# xr_vco_components_manual_rt1-V2.net
KiCad netlist of a schematic drawn in EAGLE
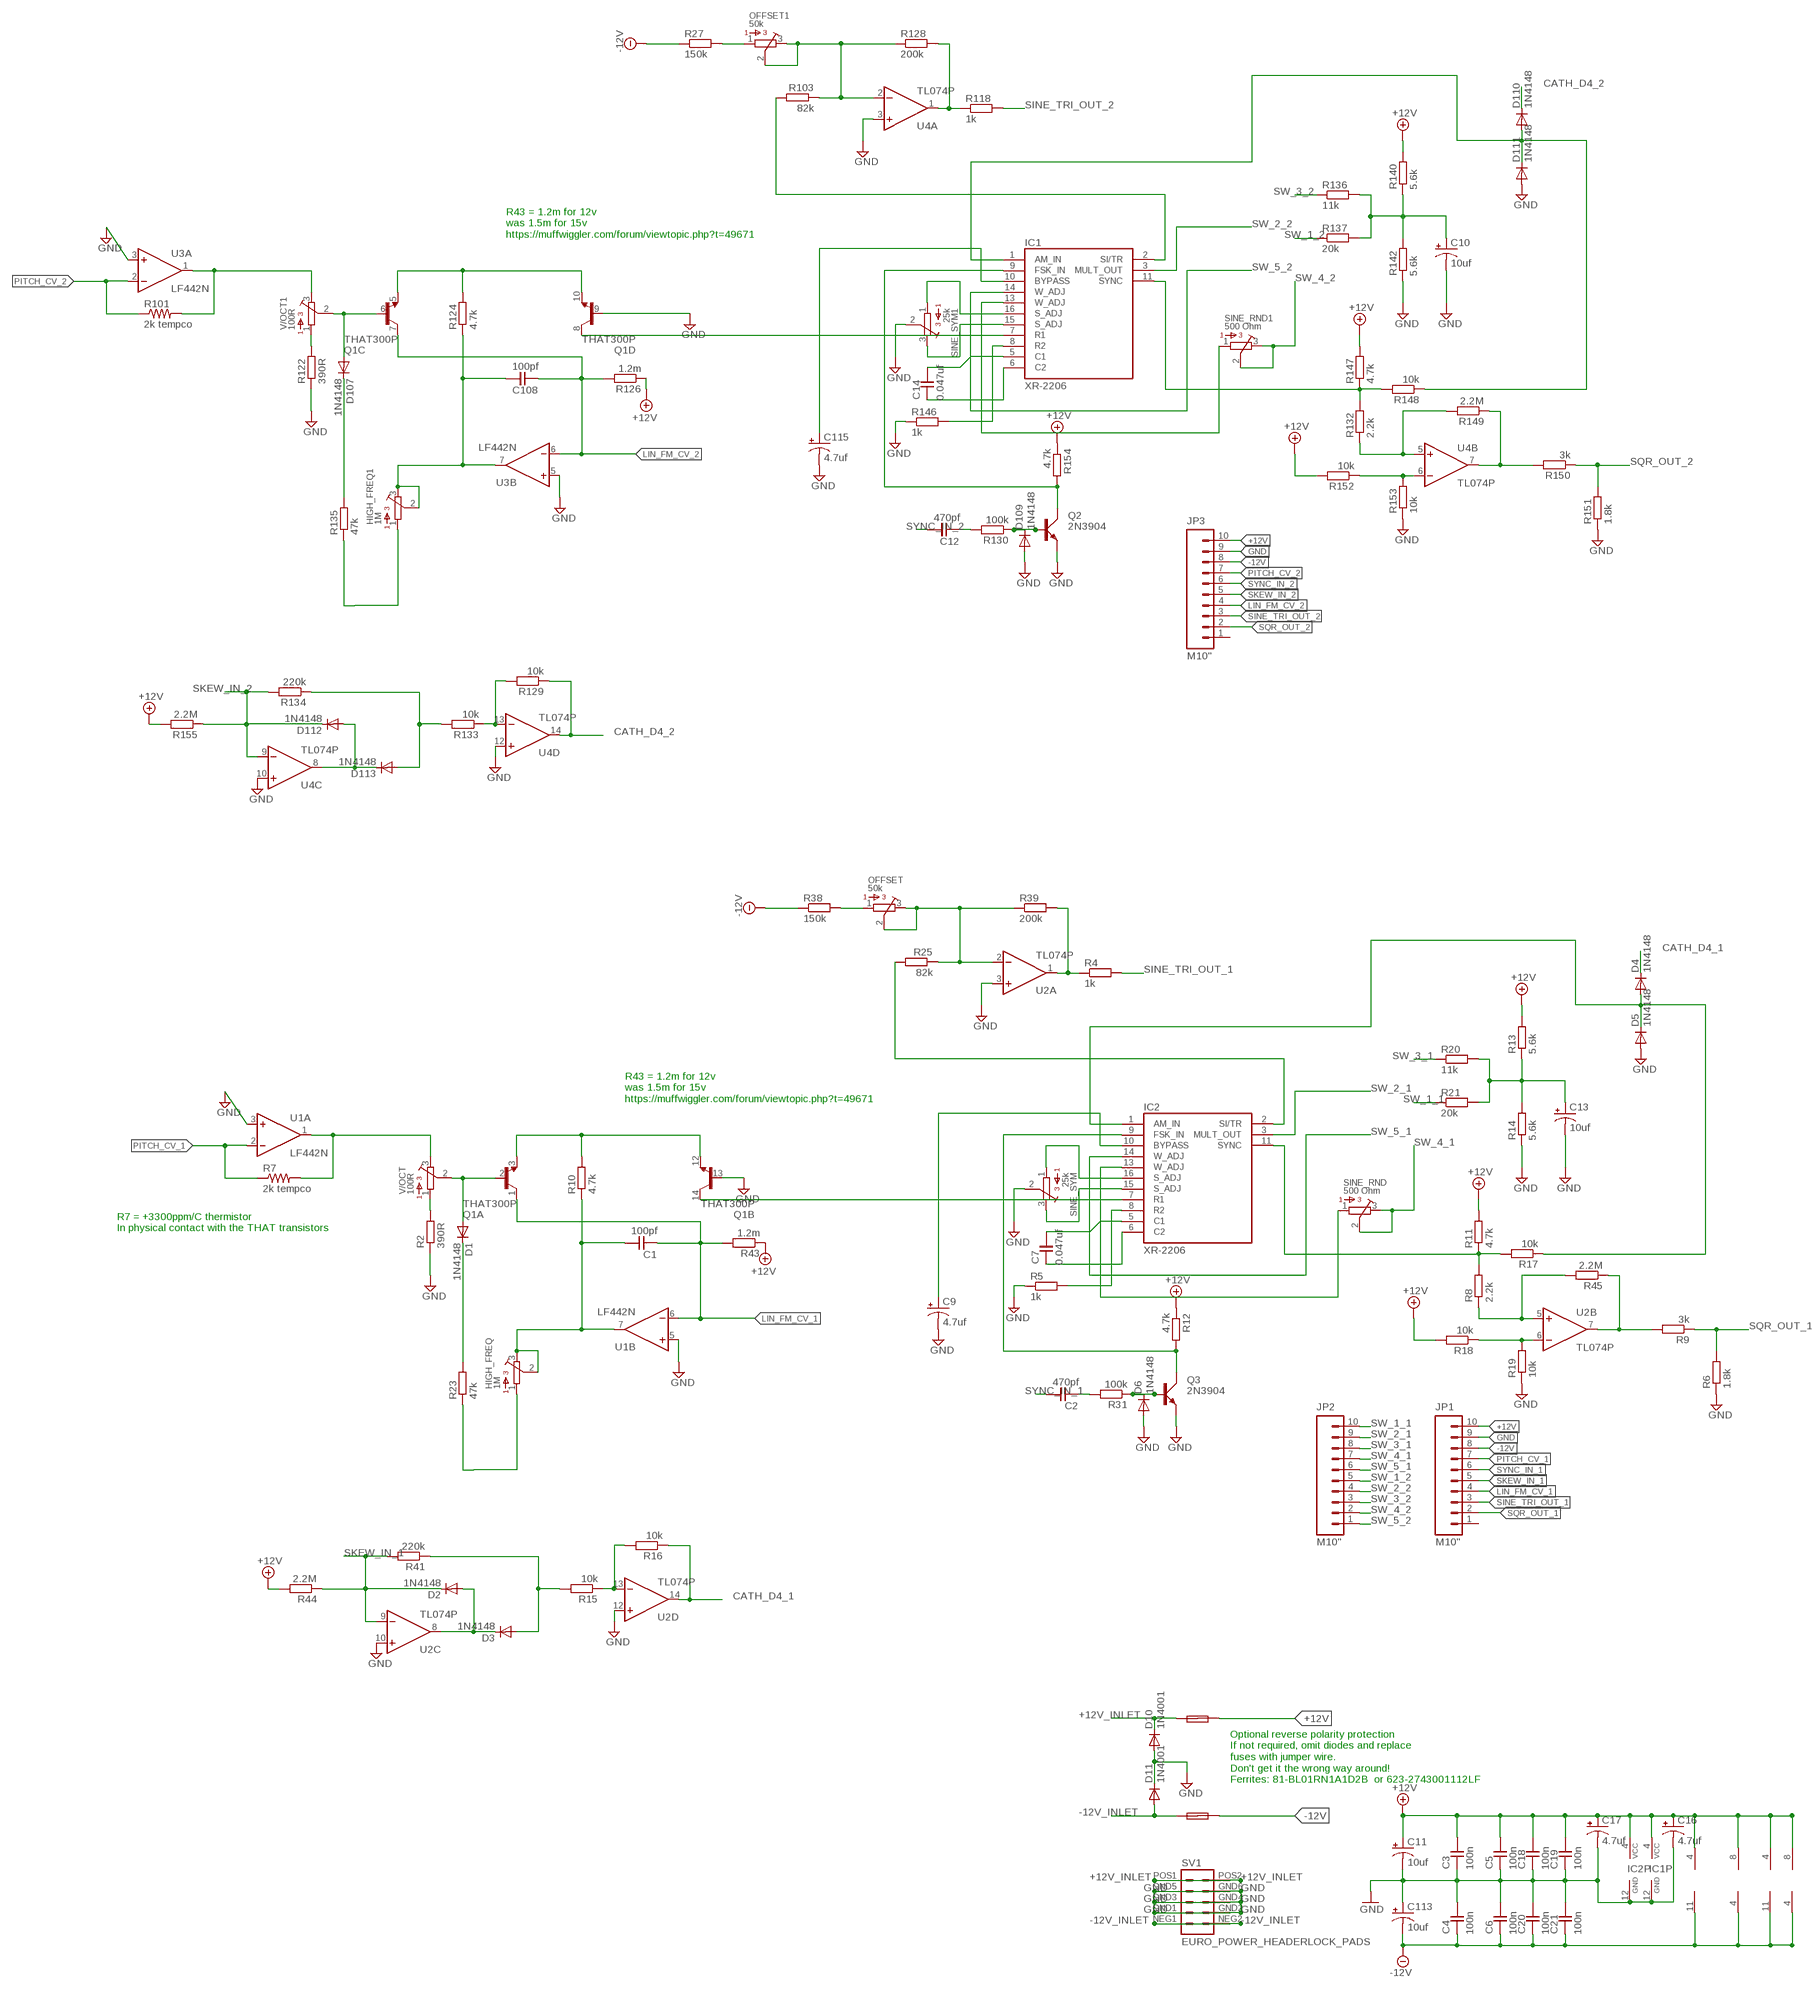
[diagram p0: schematic, sheet 1]

(export (version "E")
  (design (tool "Eeschema 10.0.6"))
  (components
    (comp (ref "C1")
      (value "100pf")
      (footprint "eagle-import:C050-024X044")
      (libsource (lib "eagle-import") (part "C-EU050-024X044"))
    )
    (comp (ref "C2")
      (value "470pf")
      (footprint "eagle-import:C050-024X044")
      (libsource (lib "eagle-import") (part "C-EU050-024X044"))
    )
    (comp (ref "C3")
      (value "100n")
      (footprint "eagle-import:C050-024X044")
      (libsource (lib "eagle-import") (part "C-EU050-024X044"))
    )
    (comp (ref "C4")
      (value "100n")
      (footprint "eagle-import:C050-024X044")
      (libsource (lib "eagle-import") (part "C-EU050-024X044"))
    )
    (comp (ref "C5")
      (value "100n")
      (footprint "eagle-import:C050-024X044")
      (libsource (lib "eagle-import") (part "C-EU050-024X044"))
    )
    (comp (ref "C6")
      (value "100n")
      (footprint "eagle-import:C050-024X044")
      (libsource (lib "eagle-import") (part "C-EU050-024X044"))
    )
    (comp (ref "C7")
      (value "0.047uf")
      (footprint "eagle-import:C050-024X044")
      (libsource (lib "eagle-import") (part "C-EU050-024X044"))
    )
    (comp (ref "C9")
      (value "4.7uf")
      (footprint "eagle-import:CPOL-RADIAL-10UF-25V")
      (libsource (lib "eagle-import") (part "CAP_POLPTH2"))
    )
    (comp (ref "C10")
      (value "10uf")
      (footprint "eagle-import:CPOL-RADIAL-10UF-25V")
      (libsource (lib "eagle-import") (part "CAP_POLPTH2"))
    )
    (comp (ref "C11")
      (value "10uf")
      (footprint "eagle-import:CPOL-RADIAL-10UF-25V")
      (libsource (lib "eagle-import") (part "CAP_POLPTH2"))
    )
    (comp (ref "C12")
      (value "470pf")
      (footprint "eagle-import:C050-024X044")
      (libsource (lib "eagle-import") (part "C-EU050-024X044"))
    )
    (comp (ref "C13")
      (value "10uf")
      (footprint "eagle-import:CPOL-RADIAL-10UF-25V")
      (libsource (lib "eagle-import") (part "CAP_POLPTH2"))
    )
    (comp (ref "C14")
      (value "0.047uf")
      (footprint "eagle-import:C050-024X044")
      (libsource (lib "eagle-import") (part "C-EU050-024X044"))
    )
    (comp (ref "C16")
      (value "4.7uf")
      (footprint "eagle-import:CPOL-RADIAL-10UF-25V")
      (libsource (lib "eagle-import") (part "CAP_POLPTH2"))
    )
    (comp (ref "C17")
      (value "4.7uf")
      (footprint "eagle-import:CPOL-RADIAL-10UF-25V")
      (libsource (lib "eagle-import") (part "CAP_POLPTH2"))
    )
    (comp (ref "C18")
      (value "100n")
      (footprint "eagle-import:C050-024X044")
      (libsource (lib "eagle-import") (part "C-EU050-024X044"))
    )
    (comp (ref "C19")
      (value "100n")
      (footprint "eagle-import:C050-024X044")
      (libsource (lib "eagle-import") (part "C-EU050-024X044"))
    )
    (comp (ref "C20")
      (value "100n")
      (footprint "eagle-import:C050-024X044")
      (libsource (lib "eagle-import") (part "C-EU050-024X044"))
    )
    (comp (ref "C21")
      (value "100n")
      (footprint "eagle-import:C050-024X044")
      (libsource (lib "eagle-import") (part "C-EU050-024X044"))
    )
    (comp (ref "C108")
      (value "100pf")
      (footprint "eagle-import:C050-024X044")
      (libsource (lib "eagle-import") (part "C-EU050-024X044"))
    )
    (comp (ref "C113")
      (value "10uf")
      (footprint "eagle-import:CPOL-RADIAL-10UF-25V")
      (libsource (lib "eagle-import") (part "CAP_POLPTH2"))
    )
    (comp (ref "C115")
      (value "4.7uf")
      (footprint "eagle-import:CPOL-RADIAL-10UF-25V")
      (libsource (lib "eagle-import") (part "CAP_POLPTH2"))
    )
    (comp (ref "D1")
      (value "1N4148")
      (footprint "eagle-import:DO35-7")
      (libsource (lib "eagle-import") (part "SMALL_DIODEDO35-7"))
    )
    (comp (ref "D2")
      (value "1N4148")
      (footprint "eagle-import:DO35-7")
      (libsource (lib "eagle-import") (part "SMALL_DIODEDO35-7"))
    )
    (comp (ref "D3")
      (value "1N4148")
      (footprint "eagle-import:DO35-7")
      (libsource (lib "eagle-import") (part "SMALL_DIODEDO35-7"))
    )
    (comp (ref "D4")
      (value "1N4148")
      (footprint "eagle-import:DO35-7")
      (libsource (lib "eagle-import") (part "SMALL_DIODEDO35-7"))
    )
    (comp (ref "D5")
      (value "1N4148")
      (footprint "eagle-import:DO35-7")
      (libsource (lib "eagle-import") (part "SMALL_DIODEDO35-7"))
    )
    (comp (ref "D6")
      (value "1N4148")
      (footprint "eagle-import:DO35-7")
      (libsource (lib "eagle-import") (part "SMALL_DIODEDO35-7"))
    )
    (comp (ref "D10")
      (value "1N4001")
      (footprint "eagle-import:DO41-10")
      (libsource (lib "eagle-import") (part "1N4004"))
    )
    (comp (ref "D11")
      (value "1N4001")
      (footprint "eagle-import:DO41-10")
      (libsource (lib "eagle-import") (part "1N4004"))
    )
    (comp (ref "D107")
      (value "1N4148")
      (footprint "eagle-import:DO35-7")
      (libsource (lib "eagle-import") (part "SMALL_DIODEDO35-7"))
    )
    (comp (ref "D109")
      (value "1N4148")
      (footprint "eagle-import:DO35-7")
      (libsource (lib "eagle-import") (part "SMALL_DIODEDO35-7"))
    )
    (comp (ref "D110")
      (value "1N4148")
      (footprint "eagle-import:DO35-7")
      (libsource (lib "eagle-import") (part "SMALL_DIODEDO35-7"))
    )
    (comp (ref "D111")
      (value "1N4148")
      (footprint "eagle-import:DO35-7")
      (libsource (lib "eagle-import") (part "SMALL_DIODEDO35-7"))
    )
    (comp (ref "D112")
      (value "1N4148")
      (footprint "eagle-import:DO35-7")
      (libsource (lib "eagle-import") (part "SMALL_DIODEDO35-7"))
    )
    (comp (ref "D113")
      (value "1N4148")
      (footprint "eagle-import:DO35-7")
      (libsource (lib "eagle-import") (part "SMALL_DIODEDO35-7"))
    )
    (comp (ref "F1")
      (value "FUSE")
      (footprint "eagle-import:C050H075X075")
      (libsource (lib "eagle-import") (part "PTC_FUSEPOLY_FUSE"))
    )
    (comp (ref "F2")
      (value "FUSE")
      (footprint "eagle-import:C050H075X075")
      (libsource (lib "eagle-import") (part "PTC_FUSEPOLY_FUSE"))
    )
    (comp (ref "HIGH_FREQ")
      (value "1M")
      (footprint "eagle-import:BOURNS_3362P_TRIMMER")
      (libsource (lib "eagle-import") (part "BOURNS_3362P_TRIMMERP"))
    )
    (comp (ref "HIGH_FREQ1")
      (value "1M")
      (footprint "eagle-import:BOURNS_3362P_TRIMMER")
      (libsource (lib "eagle-import") (part "BOURNS_3362P_TRIMMERP"))
    )
    (comp (ref "IC1")
      (value "XR-2206")
      (footprint "eagle-import:DIL16")
      (libsource (lib "eagle-import") (part "XR-2206"))
    )
    (comp (ref "IC2")
      (value "XR-2206")
      (footprint "eagle-import:DIL16")
      (libsource (lib "eagle-import") (part "XR-2206"))
    )
    (comp (ref "JP1")
      (value "M10\"")
      (footprint "eagle-import:1X10")
      (libsource (lib "eagle-import") (part "M10{dblquote}"))
    )
    (comp (ref "JP2")
      (value "M10\"")
      (footprint "eagle-import:1X10")
      (libsource (lib "eagle-import") (part "M10{dblquote}"))
    )
    (comp (ref "JP3")
      (value "M10\"")
      (footprint "eagle-import:1X10")
      (libsource (lib "eagle-import") (part "M10{dblquote}"))
    )
    (comp (ref "OFFSET")
      (value "50k")
      (footprint "eagle-import:BOURNS_3362P_TRIMMER")
      (libsource (lib "eagle-import") (part "BOURNS_3362P_TRIMMERP"))
    )
    (comp (ref "OFFSET1")
      (value "50k")
      (footprint "eagle-import:BOURNS_3362P_TRIMMER")
      (libsource (lib "eagle-import") (part "BOURNS_3362P_TRIMMERP"))
    )
    (comp (ref "Q1")
      (value "THAT300P")
      (footprint "eagle-import:DIL14")
      (libsource (lib "eagle-import") (part "THAT300P"))
    )
    (comp (ref "Q2")
      (value "2N3904")
      (footprint "eagle-import:TO92D")
      (libsource (lib "eagle-import") (part "2N3904"))
    )
    (comp (ref "Q3")
      (value "2N3904")
      (footprint "eagle-import:TO92D")
      (libsource (lib "eagle-import") (part "2N3904"))
    )
    (comp (ref "R2")
      (value "390R")
      (footprint "eagle-import:7MM_RESISTOR")
      (libsource (lib "eagle-import") (part "RESISTOR7MM"))
    )
    (comp (ref "R4")
      (value "1k")
      (footprint "eagle-import:7MM_RESISTOR")
      (libsource (lib "eagle-import") (part "RESISTOR7MM"))
    )
    (comp (ref "R5")
      (value "1k")
      (footprint "eagle-import:7MM_RESISTOR")
      (libsource (lib "eagle-import") (part "RESISTOR7MM"))
    )
    (comp (ref "R6")
      (value "1.8k")
      (footprint "eagle-import:7MM_RESISTOR")
      (libsource (lib "eagle-import") (part "RESISTOR7MM"))
    )
    (comp (ref "R7")
      (value "2k tempco")
      (footprint "eagle-import:0309_12")
      (libsource (lib "eagle-import") (part "R-US_0309/12"))
    )
    (comp (ref "R8")
      (value "2.2k")
      (footprint "eagle-import:7MM_RESISTOR")
      (libsource (lib "eagle-import") (part "RESISTOR7MM"))
    )
    (comp (ref "R9")
      (value "3k")
      (footprint "eagle-import:7MM_RESISTOR")
      (libsource (lib "eagle-import") (part "RESISTOR7MM"))
    )
    (comp (ref "R10")
      (value "4.7k")
      (footprint "eagle-import:7MM_RESISTOR")
      (libsource (lib "eagle-import") (part "RESISTOR7MM"))
    )
    (comp (ref "R11")
      (value "4.7k")
      (footprint "eagle-import:7MM_RESISTOR")
      (libsource (lib "eagle-import") (part "RESISTOR7MM"))
    )
    (comp (ref "R12")
      (value "4.7k")
      (footprint "eagle-import:7MM_RESISTOR")
      (libsource (lib "eagle-import") (part "RESISTOR7MM"))
    )
    (comp (ref "R13")
      (value "5.6k")
      (footprint "eagle-import:7MM_RESISTOR")
      (libsource (lib "eagle-import") (part "RESISTOR7MM"))
    )
    (comp (ref "R14")
      (value "5.6k")
      (footprint "eagle-import:7MM_RESISTOR")
      (libsource (lib "eagle-import") (part "RESISTOR7MM"))
    )
    (comp (ref "R15")
      (value "10k")
      (footprint "eagle-import:7MM_RESISTOR")
      (libsource (lib "eagle-import") (part "RESISTOR7MM"))
    )
    (comp (ref "R16")
      (value "10k")
      (footprint "eagle-import:7MM_RESISTOR")
      (libsource (lib "eagle-import") (part "RESISTOR7MM"))
    )
    (comp (ref "R17")
      (value "10k")
      (footprint "eagle-import:7MM_RESISTOR")
      (libsource (lib "eagle-import") (part "RESISTOR7MM"))
    )
    (comp (ref "R18")
      (value "10k")
      (footprint "eagle-import:7MM_RESISTOR")
      (libsource (lib "eagle-import") (part "RESISTOR7MM"))
    )
    (comp (ref "R19")
      (value "10k")
      (footprint "eagle-import:7MM_RESISTOR")
      (libsource (lib "eagle-import") (part "RESISTOR7MM"))
    )
    (comp (ref "R20")
      (value "11k")
      (footprint "eagle-import:7MM_RESISTOR")
      (libsource (lib "eagle-import") (part "RESISTOR7MM"))
    )
    (comp (ref "R21")
      (value "20k")
      (footprint "eagle-import:7MM_RESISTOR")
      (libsource (lib "eagle-import") (part "RESISTOR7MM"))
    )
    (comp (ref "R23")
      (value "47k")
      (footprint "eagle-import:7MM_RESISTOR")
      (libsource (lib "eagle-import") (part "RESISTOR7MM"))
    )
    (comp (ref "R25")
      (value "82k")
      (footprint "eagle-import:7MM_RESISTOR")
      (libsource (lib "eagle-import") (part "RESISTOR7MM"))
    )
    (comp (ref "R27")
      (value "150k")
      (footprint "eagle-import:7MM_RESISTOR")
      (libsource (lib "eagle-import") (part "RESISTOR7MM"))
    )
    (comp (ref "R31")
      (value "100k")
      (footprint "eagle-import:7MM_RESISTOR")
      (libsource (lib "eagle-import") (part "RESISTOR7MM"))
    )
    (comp (ref "R38")
      (value "150k")
      (footprint "eagle-import:7MM_RESISTOR")
      (libsource (lib "eagle-import") (part "RESISTOR7MM"))
    )
    (comp (ref "R39")
      (value "200k")
      (footprint "eagle-import:7MM_RESISTOR")
      (libsource (lib "eagle-import") (part "RESISTOR7MM"))
    )
    (comp (ref "R41")
      (value "220k")
      (footprint "eagle-import:7MM_RESISTOR")
      (libsource (lib "eagle-import") (part "RESISTOR7MM"))
    )
    (comp (ref "R43")
      (value "1.2m")
      (footprint "eagle-import:7MM_RESISTOR")
      (libsource (lib "eagle-import") (part "RESISTOR7MM"))
    )
    (comp (ref "R44")
      (value "2.2M")
      (footprint "eagle-import:7MM_RESISTOR")
      (libsource (lib "eagle-import") (part "RESISTOR7MM"))
    )
    (comp (ref "R45")
      (value "2.2M")
      (footprint "eagle-import:7MM_RESISTOR")
      (libsource (lib "eagle-import") (part "RESISTOR7MM"))
    )
    (comp (ref "R101")
      (value "2k tempco")
      (footprint "eagle-import:0309_12")
      (libsource (lib "eagle-import") (part "R-US_0309/12"))
    )
    (comp (ref "R103")
      (value "82k")
      (footprint "eagle-import:7MM_RESISTOR")
      (libsource (lib "eagle-import") (part "RESISTOR7MM"))
    )
    (comp (ref "R118")
      (value "1k")
      (footprint "eagle-import:7MM_RESISTOR")
      (libsource (lib "eagle-import") (part "RESISTOR7MM"))
    )
    (comp (ref "R122")
      (value "390R")
      (footprint "eagle-import:7MM_RESISTOR")
      (libsource (lib "eagle-import") (part "RESISTOR7MM"))
    )
    (comp (ref "R124")
      (value "4.7k")
      (footprint "eagle-import:7MM_RESISTOR")
      (libsource (lib "eagle-import") (part "RESISTOR7MM"))
    )
    (comp (ref "R126")
      (value "1.2m")
      (footprint "eagle-import:7MM_RESISTOR")
      (libsource (lib "eagle-import") (part "RESISTOR7MM"))
    )
    (comp (ref "R128")
      (value "200k")
      (footprint "eagle-import:7MM_RESISTOR")
      (libsource (lib "eagle-import") (part "RESISTOR7MM"))
    )
    (comp (ref "R129")
      (value "10k")
      (footprint "eagle-import:7MM_RESISTOR")
      (libsource (lib "eagle-import") (part "RESISTOR7MM"))
    )
    (comp (ref "R130")
      (value "100k")
      (footprint "eagle-import:7MM_RESISTOR")
      (libsource (lib "eagle-import") (part "RESISTOR7MM"))
    )
    (comp (ref "R132")
      (value "2.2k")
      (footprint "eagle-import:7MM_RESISTOR")
      (libsource (lib "eagle-import") (part "RESISTOR7MM"))
    )
    (comp (ref "R133")
      (value "10k")
      (footprint "eagle-import:7MM_RESISTOR")
      (libsource (lib "eagle-import") (part "RESISTOR7MM"))
    )
    (comp (ref "R134")
      (value "220k")
      (footprint "eagle-import:7MM_RESISTOR")
      (libsource (lib "eagle-import") (part "RESISTOR7MM"))
    )
    (comp (ref "R135")
      (value "47k")
      (footprint "eagle-import:7MM_RESISTOR")
      (libsource (lib "eagle-import") (part "RESISTOR7MM"))
    )
    (comp (ref "R136")
      (value "11k")
      (footprint "eagle-import:7MM_RESISTOR")
      (libsource (lib "eagle-import") (part "RESISTOR7MM"))
    )
    (comp (ref "R137")
      (value "20k")
      (footprint "eagle-import:7MM_RESISTOR")
      (libsource (lib "eagle-import") (part "RESISTOR7MM"))
    )
    (comp (ref "R140")
      (value "5.6k")
      (footprint "eagle-import:7MM_RESISTOR")
      (libsource (lib "eagle-import") (part "RESISTOR7MM"))
    )
    (comp (ref "R142")
      (value "5.6k")
      (footprint "eagle-import:7MM_RESISTOR")
      (libsource (lib "eagle-import") (part "RESISTOR7MM"))
    )
    (comp (ref "R146")
      (value "1k")
      (footprint "eagle-import:7MM_RESISTOR")
      (libsource (lib "eagle-import") (part "RESISTOR7MM"))
    )
    (comp (ref "R147")
      (value "4.7k")
      (footprint "eagle-import:7MM_RESISTOR")
      (libsource (lib "eagle-import") (part "RESISTOR7MM"))
    )
    (comp (ref "R148")
      (value "10k")
      (footprint "eagle-import:7MM_RESISTOR")
      (libsource (lib "eagle-import") (part "RESISTOR7MM"))
    )
    (comp (ref "R149")
      (value "2.2M")
      (footprint "eagle-import:7MM_RESISTOR")
      (libsource (lib "eagle-import") (part "RESISTOR7MM"))
    )
    (comp (ref "R150")
      (value "3k")
      (footprint "eagle-import:7MM_RESISTOR")
      (libsource (lib "eagle-import") (part "RESISTOR7MM"))
    )
    (comp (ref "R151")
      (value "1.8k")
      (footprint "eagle-import:7MM_RESISTOR")
      (libsource (lib "eagle-import") (part "RESISTOR7MM"))
    )
    (comp (ref "R152")
      (value "10k")
      (footprint "eagle-import:7MM_RESISTOR")
      (libsource (lib "eagle-import") (part "RESISTOR7MM"))
    )
    (comp (ref "R153")
      (value "10k")
      (footprint "eagle-import:7MM_RESISTOR")
      (libsource (lib "eagle-import") (part "RESISTOR7MM"))
    )
    (comp (ref "R154")
      (value "4.7k")
      (footprint "eagle-import:7MM_RESISTOR")
      (libsource (lib "eagle-import") (part "RESISTOR7MM"))
    )
    (comp (ref "R155")
      (value "2.2M")
      (footprint "eagle-import:7MM_RESISTOR")
      (libsource (lib "eagle-import") (part "RESISTOR7MM"))
    )
    (comp (ref "SINE_RND")
      (value "500 Ohm")
      (footprint "eagle-import:BOURNS_3362P_TRIMMER")
      (libsource (lib "eagle-import") (part "BOURNS_3362P_TRIMMERP"))
    )
    (comp (ref "SINE_RND1")
      (value "500 Ohm")
      (footprint "eagle-import:BOURNS_3362P_TRIMMER")
      (libsource (lib "eagle-import") (part "BOURNS_3362P_TRIMMERP"))
    )
    (comp (ref "SINE_SYM")
      (value "25k")
      (footprint "eagle-import:BOURNS_3362P_TRIMMER")
      (libsource (lib "eagle-import") (part "BOURNS_3362P_TRIMMERP"))
    )
    (comp (ref "SINE_SYM1")
      (value "25k")
      (footprint "eagle-import:BOURNS_3362P_TRIMMER")
      (libsource (lib "eagle-import") (part "BOURNS_3362P_TRIMMERP"))
    )
    (comp (ref "SV1")
      (value "EURO_POWER_HEADERLOCK_PADS")
      (footprint "eagle-import:EURO_PWR_HEADER_LOCK")
      (libsource (lib "eagle-import") (part "EURO_POWER_HEADERLOCK_PADS"))
    )
    (comp (ref "U1")
      (value "LF442N")
      (footprint "eagle-import:DIL08")
      (libsource (lib "eagle-import") (part "LF442N"))
    )
    (comp (ref "U2")
      (value "TL074P")
      (footprint "eagle-import:DIL14")
      (libsource (lib "eagle-import") (part "TL074P"))
    )
    (comp (ref "U3")
      (value "LF442N")
      (footprint "eagle-import:DIL08")
      (libsource (lib "eagle-import") (part "LF442N"))
    )
    (comp (ref "U4")
      (value "TL074P")
      (footprint "eagle-import:DIL14")
      (libsource (lib "eagle-import") (part "TL074P"))
    )
    (comp (ref "V/OCT")
      (value "100R")
      (footprint "eagle-import:BOURNS_3362P_TRIMMER")
      (libsource (lib "eagle-import") (part "BOURNS_3362P_TRIMMERP"))
    )
    (comp (ref "V/OCT1")
      (value "100R")
      (footprint "eagle-import:BOURNS_3362P_TRIMMER")
      (libsource (lib "eagle-import") (part "BOURNS_3362P_TRIMMERP"))
    )
  )
  (nets
    (net (code "1") (name "+12V") (class "Default")
      (node (ref "C11") (pin "1") (pinfunction "+_1") (pintype "passive"))
      (node (ref "C16") (pin "1") (pinfunction "+_1") (pintype "passive"))
      (node (ref "C17") (pin "1") (pinfunction "+_1") (pintype "passive"))
      (node (ref "C18") (pin "1") (pinfunction "1_1") (pintype "passive"))
      (node (ref "C19") (pin "1") (pinfunction "1_1") (pintype "passive"))
      (node (ref "C3") (pin "1") (pinfunction "1_1") (pintype "passive"))
      (node (ref "C5") (pin "1") (pinfunction "1_1") (pintype "passive"))
      (node (ref "F1") (pin "2") (pinfunction "P$2_2") (pintype "bidirectional"))
      (node (ref "IC1") (pin "4") (pinfunction "VCC_4") (pintype "power_in"))
      (node (ref "IC2") (pin "4") (pinfunction "VCC_4") (pintype "power_in"))
      (node (ref "JP1") (pin "10") (pinfunction "10_10") (pintype "passive"))
      (node (ref "JP3") (pin "10") (pinfunction "10_10") (pintype "passive"))
      (node (ref "R11") (pin "2") (pinfunction "2_2") (pintype "passive"))
      (node (ref "R12") (pin "1") (pinfunction "1_1") (pintype "passive"))
      (node (ref "R126") (pin "1") (pinfunction "1_1") (pintype "passive"))
      (node (ref "R13") (pin "2") (pinfunction "2_2") (pintype "passive"))
      (node (ref "R140") (pin "2") (pinfunction "2_2") (pintype "passive"))
      (node (ref "R147") (pin "2") (pinfunction "2_2") (pintype "passive"))
      (node (ref "R152") (pin "2") (pinfunction "2_2") (pintype "passive"))
      (node (ref "R154") (pin "1") (pinfunction "1_1") (pintype "passive"))
      (node (ref "R155") (pin "2") (pinfunction "2_2") (pintype "passive"))
      (node (ref "R18") (pin "2") (pinfunction "2_2") (pintype "passive"))
      (node (ref "R43") (pin "1") (pinfunction "1_1") (pintype "passive"))
      (node (ref "R44") (pin "2") (pinfunction "2_2") (pintype "passive"))
      (node (ref "U1") (pin "8") (pinfunction "V+_8") (pintype "power_in"))
      (node (ref "U2") (pin "4") (pinfunction "V+_4") (pintype "power_in"))
      (node (ref "U3") (pin "8") (pinfunction "V+_8") (pintype "power_in"))
      (node (ref "U4") (pin "4") (pinfunction "V+_4") (pintype "power_in"))
    )
    (net (code "2") (name "-12V") (class "Default")
      (node (ref "C113") (pin "2") (pinfunction "-_2") (pintype "passive"))
      (node (ref "C20") (pin "2") (pinfunction "2_2") (pintype "passive"))
      (node (ref "C21") (pin "2") (pinfunction "2_2") (pintype "passive"))
      (node (ref "C4") (pin "2") (pinfunction "2_2") (pintype "passive"))
      (node (ref "C6") (pin "2") (pinfunction "2_2") (pintype "passive"))
      (node (ref "F2") (pin "2") (pinfunction "P$2_2") (pintype "bidirectional"))
      (node (ref "JP1") (pin "8") (pinfunction "8_8") (pintype "passive"))
      (node (ref "JP3") (pin "8") (pinfunction "8_8") (pintype "passive"))
      (node (ref "R27") (pin "1") (pinfunction "1_1") (pintype "passive"))
      (node (ref "R38") (pin "1") (pinfunction "1_1") (pintype "passive"))
      (node (ref "U1") (pin "4") (pinfunction "V-_4") (pintype "power_in"))
      (node (ref "U2") (pin "11") (pinfunction "V-_11") (pintype "power_in"))
      (node (ref "U3") (pin "4") (pinfunction "V-_4") (pintype "power_in"))
      (node (ref "U4") (pin "11") (pinfunction "V-_11") (pintype "power_in"))
    )
    (net (code "3") (name "/+12V_INLET") (class "Default")
      (node (ref "D10") (pin "C") (pinfunction "C_C") (pintype "passive"))
      (node (ref "F1") (pin "1") (pinfunction "P$1_1") (pintype "bidirectional"))
      (node (ref "SV1") (pin "POS1") (pinfunction "10_POS1") (pintype "passive"))
      (node (ref "SV1") (pin "POS2") (pinfunction "9_POS2") (pintype "passive"))
    )
    (net (code "4") (name "/-12V_INLET") (class "Default")
      (node (ref "D11") (pin "A") (pinfunction "A_A") (pintype "passive"))
      (node (ref "F2") (pin "1") (pinfunction "P$1_1") (pintype "bidirectional"))
      (node (ref "SV1") (pin "NEG1") (pinfunction "2_NEG1") (pintype "passive"))
      (node (ref "SV1") (pin "NEG2") (pinfunction "1_NEG2") (pintype "passive"))
    )
    (net (code "5") (name "/CATH_D4_1") (class "Default")
      (node (ref "D4") (pin "C") (pinfunction "C_C") (pintype "passive"))
      (node (ref "R16") (pin "1") (pinfunction "1_1") (pintype "passive"))
      (node (ref "U2") (pin "14") (pinfunction "OUT_14") (pintype "output"))
    )
    (net (code "6") (name "/CATH_D4_2") (class "Default")
      (node (ref "D110") (pin "C") (pinfunction "C_C") (pintype "passive"))
      (node (ref "R129") (pin "1") (pinfunction "1_1") (pintype "passive"))
      (node (ref "U4") (pin "14") (pinfunction "OUT_14") (pintype "output"))
    )
    (net (code "7") (name "/SW_1_1") (class "Default")
      (node (ref "JP2") (pin "10") (pinfunction "10_10") (pintype "passive"))
      (node (ref "R21") (pin "1") (pinfunction "1_1") (pintype "passive"))
    )
    (net (code "8") (name "/SW_1_2") (class "Default")
      (node (ref "JP2") (pin "5") (pinfunction "5_5") (pintype "passive"))
      (node (ref "R137") (pin "1") (pinfunction "1_1") (pintype "passive"))
    )
    (net (code "9") (name "/SW_2_1") (class "Default")
      (node (ref "IC2") (pin "3") (pinfunction "MULT_OUT_3") (pintype "output"))
      (node (ref "JP2") (pin "9") (pinfunction "9_9") (pintype "passive"))
    )
    (net (code "10") (name "/SW_2_2") (class "Default")
      (node (ref "IC1") (pin "3") (pinfunction "MULT_OUT_3") (pintype "output"))
      (node (ref "JP2") (pin "4") (pinfunction "4_4") (pintype "passive"))
    )
    (net (code "11") (name "/SW_3_1") (class "Default")
      (node (ref "JP2") (pin "8") (pinfunction "8_8") (pintype "passive"))
      (node (ref "R20") (pin "1") (pinfunction "1_1") (pintype "passive"))
    )
    (net (code "12") (name "/SW_3_2") (class "Default")
      (node (ref "JP2") (pin "3") (pinfunction "3_3") (pintype "passive"))
      (node (ref "R136") (pin "1") (pinfunction "1_1") (pintype "passive"))
    )
    (net (code "13") (name "/SW_4_1") (class "Default")
      (node (ref "JP2") (pin "7") (pinfunction "7_7") (pintype "passive"))
      (node (ref "SINE_RND") (pin "2") (pinfunction "2_2") (pintype "passive"))
      (node (ref "SINE_RND") (pin "3") (pinfunction "3_3") (pintype "passive"))
    )
    (net (code "14") (name "/SW_4_2") (class "Default")
      (node (ref "JP2") (pin "2") (pinfunction "2_2") (pintype "passive"))
      (node (ref "SINE_RND1") (pin "2") (pinfunction "2_2") (pintype "passive"))
      (node (ref "SINE_RND1") (pin "3") (pinfunction "3_3") (pintype "passive"))
    )
    (net (code "15") (name "/SW_5_1") (class "Default")
      (node (ref "IC2") (pin "14") (pinfunction "W_ADJ_14") (pintype "input"))
      (node (ref "JP2") (pin "6") (pinfunction "6_6") (pintype "passive"))
    )
    (net (code "16") (name "/SW_5_2") (class "Default")
      (node (ref "IC1") (pin "14") (pinfunction "W_ADJ_14") (pintype "input"))
      (node (ref "JP2") (pin "1") (pinfunction "1_1") (pintype "passive"))
    )
    (net (code "17") (name "GND") (class "Default")
      (node (ref "C10") (pin "2") (pinfunction "-_2") (pintype "passive"))
      (node (ref "C11") (pin "2") (pinfunction "-_2") (pintype "passive"))
      (node (ref "C113") (pin "1") (pinfunction "+_1") (pintype "passive"))
      (node (ref "C115") (pin "2") (pinfunction "-_2") (pintype "passive"))
      (node (ref "C13") (pin "2") (pinfunction "-_2") (pintype "passive"))
      (node (ref "C16") (pin "2") (pinfunction "-_2") (pintype "passive"))
      (node (ref "C17") (pin "2") (pinfunction "-_2") (pintype "passive"))
      (node (ref "C18") (pin "2") (pinfunction "2_2") (pintype "passive"))
      (node (ref "C19") (pin "2") (pinfunction "2_2") (pintype "passive"))
      (node (ref "C20") (pin "1") (pinfunction "1_1") (pintype "passive"))
      (node (ref "C21") (pin "1") (pinfunction "1_1") (pintype "passive"))
      (node (ref "C3") (pin "2") (pinfunction "2_2") (pintype "passive"))
      (node (ref "C4") (pin "1") (pinfunction "1_1") (pintype "passive"))
      (node (ref "C5") (pin "2") (pinfunction "2_2") (pintype "passive"))
      (node (ref "C6") (pin "1") (pinfunction "1_1") (pintype "passive"))
      (node (ref "C9") (pin "2") (pinfunction "-_2") (pintype "passive"))
      (node (ref "D10") (pin "A") (pinfunction "A_A") (pintype "passive"))
      (node (ref "D109") (pin "A") (pinfunction "A_A") (pintype "passive"))
      (node (ref "D11") (pin "C") (pinfunction "C_C") (pintype "passive"))
      (node (ref "D111") (pin "A") (pinfunction "A_A") (pintype "passive"))
      (node (ref "D5") (pin "A") (pinfunction "A_A") (pintype "passive"))
      (node (ref "D6") (pin "A") (pinfunction "A_A") (pintype "passive"))
      (node (ref "IC1") (pin "12") (pinfunction "GND_12") (pintype "power_in"))
      (node (ref "IC2") (pin "12") (pinfunction "GND_12") (pintype "power_in"))
      (node (ref "JP1") (pin "9") (pinfunction "9_9") (pintype "passive"))
      (node (ref "JP3") (pin "9") (pinfunction "9_9") (pintype "passive"))
      (node (ref "Q1") (pin "13") (pinfunction "B_13") (pintype "passive"))
      (node (ref "Q1") (pin "9") (pinfunction "B_9") (pintype "passive"))
      (node (ref "Q2") (pin "E") (pinfunction "E_E") (pintype "passive"))
      (node (ref "Q3") (pin "E") (pinfunction "E_E") (pintype "passive"))
      (node (ref "R122") (pin "1") (pinfunction "1_1") (pintype "passive"))
      (node (ref "R14") (pin "1") (pinfunction "1_1") (pintype "passive"))
      (node (ref "R142") (pin "1") (pinfunction "1_1") (pintype "passive"))
      (node (ref "R146") (pin "1") (pinfunction "1_1") (pintype "passive"))
      (node (ref "R151") (pin "1") (pinfunction "1_1") (pintype "passive"))
      (node (ref "R153") (pin "1") (pinfunction "1_1") (pintype "passive"))
      (node (ref "R19") (pin "1") (pinfunction "1_1") (pintype "passive"))
      (node (ref "R2") (pin "1") (pinfunction "1_1") (pintype "passive"))
      (node (ref "R5") (pin "1") (pinfunction "1_1") (pintype "passive"))
      (node (ref "R6") (pin "1") (pinfunction "1_1") (pintype "passive"))
      (node (ref "SINE_SYM") (pin "2") (pinfunction "2_2") (pintype "passive"))
      (node (ref "SINE_SYM1") (pin "2") (pinfunction "2_2") (pintype "passive"))
      (node (ref "SV1") (pin "GND1") (pinfunction "4_GND1") (pintype "passive"))
      (node (ref "SV1") (pin "GND2") (pinfunction "3_GND2") (pintype "passive"))
      (node (ref "SV1") (pin "GND3") (pinfunction "6_GND3") (pintype "passive"))
      (node (ref "SV1") (pin "GND4") (pinfunction "5_GND4") (pintype "passive"))
      (node (ref "SV1") (pin "GND5") (pinfunction "8_GND5") (pintype "passive"))
      (node (ref "SV1") (pin "GND6") (pinfunction "7_GND6") (pintype "passive"))
      (node (ref "U1") (pin "3") (pinfunction "+IN_3") (pintype "input"))
      (node (ref "U1") (pin "5") (pinfunction "+IN_5") (pintype "input"))
      (node (ref "U2") (pin "10") (pinfunction "+IN_10") (pintype "input"))
      (node (ref "U2") (pin "12") (pinfunction "+IN_12") (pintype "input"))
      (node (ref "U2") (pin "3") (pinfunction "+IN_3") (pintype "input"))
      (node (ref "U3") (pin "3") (pinfunction "+IN_3") (pintype "input"))
      (node (ref "U3") (pin "5") (pinfunction "+IN_5") (pintype "input"))
      (node (ref "U4") (pin "10") (pinfunction "+IN_10") (pintype "input"))
      (node (ref "U4") (pin "12") (pinfunction "+IN_12") (pintype "input"))
      (node (ref "U4") (pin "3") (pinfunction "+IN_3") (pintype "input"))
    )
    (net (code "18") (name "LIN_FM_CV_1") (class "Default")
      (node (ref "C1") (pin "2") (pinfunction "2_2") (pintype "passive"))
      (node (ref "JP1") (pin "4") (pinfunction "4_4") (pintype "passive"))
      (node (ref "Q1") (pin "1") (pinfunction "C_1") (pintype "passive"))
      (node (ref "R43") (pin "2") (pinfunction "2_2") (pintype "passive"))
      (node (ref "U1") (pin "6") (pinfunction "-IN_6") (pintype "input"))
    )
    (net (code "19") (name "LIN_FM_CV_2") (class "Default")
      (node (ref "C108") (pin "2") (pinfunction "2_2") (pintype "passive"))
      (node (ref "JP3") (pin "4") (pinfunction "4_4") (pintype "passive"))
      (node (ref "Q1") (pin "7") (pinfunction "C_7") (pintype "passive"))
      (node (ref "R126") (pin "2") (pinfunction "2_2") (pintype "passive"))
      (node (ref "U3") (pin "6") (pinfunction "-IN_6") (pintype "input"))
    )
    (net (code "20") (name "Net-(C2-Pad2)") (class "Default")
      (node (ref "C2") (pin "2") (pinfunction "2_2") (pintype "passive"))
      (node (ref "R31") (pin "2") (pinfunction "2_2") (pintype "passive"))
    )
    (net (code "21") (name "Net-(C9-+)") (class "Default")
      (node (ref "C9") (pin "1") (pinfunction "+_1") (pintype "passive"))
      (node (ref "IC2") (pin "10") (pinfunction "BYPASS_10") (pintype "input"))
    )
    (net (code "22") (name "Net-(C10-+)") (class "Default")
      (node (ref "C10") (pin "1") (pinfunction "+_1") (pintype "passive"))
      (node (ref "R136") (pin "2") (pinfunction "2_2") (pintype "passive"))
      (node (ref "R137") (pin "2") (pinfunction "2_2") (pintype "passive"))
      (node (ref "R140") (pin "1") (pinfunction "1_1") (pintype "passive"))
      (node (ref "R142") (pin "2") (pinfunction "2_2") (pintype "passive"))
    )
    (net (code "23") (name "Net-(C12-Pad2)") (class "Default")
      (node (ref "C12") (pin "2") (pinfunction "2_2") (pintype "passive"))
      (node (ref "R130") (pin "2") (pinfunction "2_2") (pintype "passive"))
    )
    (net (code "24") (name "Net-(C13-+)") (class "Default")
      (node (ref "C13") (pin "1") (pinfunction "+_1") (pintype "passive"))
      (node (ref "R13") (pin "1") (pinfunction "1_1") (pintype "passive"))
      (node (ref "R14") (pin "2") (pinfunction "2_2") (pintype "passive"))
      (node (ref "R20") (pin "2") (pinfunction "2_2") (pintype "passive"))
      (node (ref "R21") (pin "2") (pinfunction "2_2") (pintype "passive"))
    )
    (net (code "25") (name "Net-(C115-+)") (class "Default")
      (node (ref "C115") (pin "1") (pinfunction "+_1") (pintype "passive"))
      (node (ref "IC1") (pin "10") (pinfunction "BYPASS_10") (pintype "input"))
    )
    (net (code "26") (name "Net-(D1-PadC)") (class "Default")
      (node (ref "D1") (pin "C") (pinfunction "C_C") (pintype "passive"))
      (node (ref "R23") (pin "2") (pinfunction "2_2") (pintype "passive"))
    )
    (net (code "27") (name "Net-(D3-PadA)") (class "Default")
      (node (ref "D3") (pin "A") (pinfunction "A_A") (pintype "passive"))
      (node (ref "R15") (pin "2") (pinfunction "2_2") (pintype "passive"))
      (node (ref "R41") (pin "1") (pinfunction "1_1") (pintype "passive"))
    )
    (net (code "28") (name "Net-(D6-PadC)") (class "Default")
      (node (ref "D6") (pin "C") (pinfunction "C_C") (pintype "passive"))
      (node (ref "Q3") (pin "B") (pinfunction "B_B") (pintype "passive"))
      (node (ref "R31") (pin "1") (pinfunction "1_1") (pintype "passive"))
    )
    (net (code "29") (name "Net-(D107-PadC)") (class "Default")
      (node (ref "D107") (pin "C") (pinfunction "C_C") (pintype "passive"))
      (node (ref "R135") (pin "2") (pinfunction "2_2") (pintype "passive"))
    )
    (net (code "30") (name "Net-(D109-PadC)") (class "Default")
      (node (ref "D109") (pin "C") (pinfunction "C_C") (pintype "passive"))
      (node (ref "Q2") (pin "B") (pinfunction "B_B") (pintype "passive"))
      (node (ref "R130") (pin "1") (pinfunction "1_1") (pintype "passive"))
    )
    (net (code "31") (name "Net-(D113-PadA)") (class "Default")
      (node (ref "D113") (pin "A") (pinfunction "A_A") (pintype "passive"))
      (node (ref "R133") (pin "2") (pinfunction "2_2") (pintype "passive"))
      (node (ref "R134") (pin "1") (pinfunction "1_1") (pintype "passive"))
    )
    (net (code "32") (name "Net-(HIGH_FREQ-Pad1)") (class "Default")
      (node (ref "HIGH_FREQ") (pin "1") (pinfunction "1_1") (pintype "passive"))
      (node (ref "R23") (pin "1") (pinfunction "1_1") (pintype "passive"))
    )
    (net (code "33") (name "Net-(HIGH_FREQ1-Pad1)") (class "Default")
      (node (ref "HIGH_FREQ1") (pin "1") (pinfunction "1_1") (pintype "passive"))
      (node (ref "R135") (pin "1") (pinfunction "1_1") (pintype "passive"))
    )
    (net (code "34") (name "Net-(IC1A-AM_IN)") (class "Default")
      (node (ref "D110") (pin "A") (pinfunction "A_A") (pintype "passive"))
      (node (ref "D111") (pin "C") (pinfunction "C_C") (pintype "passive"))
      (node (ref "IC1") (pin "1") (pinfunction "AM_IN_1") (pintype "input"))
      (node (ref "R148") (pin "1") (pinfunction "1_1") (pintype "passive"))
    )
    (net (code "35") (name "Net-(IC1A-C1)") (class "Default")
      (node (ref "C14") (pin "1") (pinfunction "1_1") (pintype "passive"))
      (node (ref "IC1") (pin "5") (pinfunction "C1_5") (pintype "input"))
    )
    (net (code "36") (name "Net-(IC1A-C2)") (class "Default")
      (node (ref "C14") (pin "2") (pinfunction "2_2") (pintype "passive"))
      (node (ref "IC1") (pin "6") (pinfunction "C2_6") (pintype "input"))
    )
    (net (code "37") (name "Net-(IC1A-FSK_IN)") (class "Default")
      (node (ref "IC1") (pin "9") (pinfunction "FSK_IN_9") (pintype "input"))
      (node (ref "Q2") (pin "C") (pinfunction "C_C") (pintype "passive"))
      (node (ref "R154") (pin "2") (pinfunction "2_2") (pintype "passive"))
    )
    (net (code "38") (name "Net-(IC1A-R1)") (class "Default")
      (node (ref "IC1") (pin "7") (pinfunction "R1_7") (pintype "input"))
      (node (ref "Q1") (pin "8") (pinfunction "C_8") (pintype "passive"))
    )
    (net (code "39") (name "Net-(IC1A-R2)") (class "Default")
      (node (ref "IC1") (pin "8") (pinfunction "R2_8") (pintype "input"))
      (node (ref "R146") (pin "2") (pinfunction "2_2") (pintype "passive"))
    )
    (net (code "40") (name "Net-(IC1A-SI{slash}TR)") (class "Default")
      (node (ref "IC1") (pin "2") (pinfunction "SI/TR_2") (pintype "output"))
      (node (ref "R103") (pin "2") (pinfunction "2_2") (pintype "passive"))
    )
    (net (code "41") (name "Net-(IC1A-SYNC)") (class "Default")
      (node (ref "IC1") (pin "11") (pinfunction "SYNC_11") (pintype "output"))
      (node (ref "R132") (pin "2") (pinfunction "2_2") (pintype "passive"))
      (node (ref "R147") (pin "1") (pinfunction "1_1") (pintype "passive"))
      (node (ref "R148") (pin "2") (pinfunction "2_2") (pintype "passive"))
    )
    (net (code "42") (name "Net-(IC1A-S_ADJ-Pad15)") (class "Default")
      (node (ref "IC1") (pin "15") (pinfunction "S_ADJ_15") (pintype "input"))
      (node (ref "SINE_SYM1") (pin "3") (pinfunction "3_3") (pintype "passive"))
    )
    (net (code "43") (name "Net-(IC1A-S_ADJ-Pad16)") (class "Default")
      (node (ref "IC1") (pin "16") (pinfunction "S_ADJ_16") (pintype "input"))
      (node (ref "SINE_SYM1") (pin "1") (pinfunction "1_1") (pintype "passive"))
    )
    (net (code "44") (name "Net-(IC1A-W_ADJ-Pad13)") (class "Default")
      (node (ref "IC1") (pin "13") (pinfunction "W_ADJ_13") (pintype "input"))
      (node (ref "SINE_RND1") (pin "1") (pinfunction "1_1") (pintype "passive"))
    )
    (net (code "45") (name "Net-(IC2A-AM_IN)") (class "Default")
      (node (ref "D4") (pin "A") (pinfunction "A_A") (pintype "passive"))
      (node (ref "D5") (pin "C") (pinfunction "C_C") (pintype "passive"))
      (node (ref "IC2") (pin "1") (pinfunction "AM_IN_1") (pintype "input"))
      (node (ref "R17") (pin "1") (pinfunction "1_1") (pintype "passive"))
    )
    (net (code "46") (name "Net-(IC2A-C1)") (class "Default")
      (node (ref "C7") (pin "1") (pinfunction "1_1") (pintype "passive"))
      (node (ref "IC2") (pin "5") (pinfunction "C1_5") (pintype "input"))
    )
    (net (code "47") (name "Net-(IC2A-C2)") (class "Default")
      (node (ref "C7") (pin "2") (pinfunction "2_2") (pintype "passive"))
      (node (ref "IC2") (pin "6") (pinfunction "C2_6") (pintype "input"))
    )
    (net (code "48") (name "Net-(IC2A-FSK_IN)") (class "Default")
      (node (ref "IC2") (pin "9") (pinfunction "FSK_IN_9") (pintype "input"))
      (node (ref "Q3") (pin "C") (pinfunction "C_C") (pintype "passive"))
      (node (ref "R12") (pin "2") (pinfunction "2_2") (pintype "passive"))
    )
    (net (code "49") (name "Net-(IC2A-R1)") (class "Default")
      (node (ref "IC2") (pin "7") (pinfunction "R1_7") (pintype "input"))
      (node (ref "Q1") (pin "14") (pinfunction "C_14") (pintype "passive"))
    )
    (net (code "50") (name "Net-(IC2A-R2)") (class "Default")
      (node (ref "IC2") (pin "8") (pinfunction "R2_8") (pintype "input"))
      (node (ref "R5") (pin "2") (pinfunction "2_2") (pintype "passive"))
    )
    (net (code "51") (name "Net-(IC2A-SI{slash}TR)") (class "Default")
      (node (ref "IC2") (pin "2") (pinfunction "SI/TR_2") (pintype "output"))
      (node (ref "R25") (pin "2") (pinfunction "2_2") (pintype "passive"))
    )
    (net (code "52") (name "Net-(IC2A-SYNC)") (class "Default")
      (node (ref "IC2") (pin "11") (pinfunction "SYNC_11") (pintype "output"))
      (node (ref "R11") (pin "1") (pinfunction "1_1") (pintype "passive"))
      (node (ref "R17") (pin "2") (pinfunction "2_2") (pintype "passive"))
      (node (ref "R8") (pin "2") (pinfunction "2_2") (pintype "passive"))
    )
    (net (code "53") (name "Net-(IC2A-S_ADJ-Pad15)") (class "Default")
      (node (ref "IC2") (pin "15") (pinfunction "S_ADJ_15") (pintype "input"))
      (node (ref "SINE_SYM") (pin "3") (pinfunction "3_3") (pintype "passive"))
    )
    (net (code "54") (name "Net-(IC2A-S_ADJ-Pad16)") (class "Default")
      (node (ref "IC2") (pin "16") (pinfunction "S_ADJ_16") (pintype "input"))
      (node (ref "SINE_SYM") (pin "1") (pinfunction "1_1") (pintype "passive"))
    )
    (net (code "55") (name "Net-(IC2A-W_ADJ-Pad13)") (class "Default")
      (node (ref "IC2") (pin "13") (pinfunction "W_ADJ_13") (pintype "input"))
      (node (ref "SINE_RND") (pin "1") (pinfunction "1_1") (pintype "passive"))
    )
    (net (code "56") (name "Net-(OFFSET-Pad1)") (class "Default")
      (node (ref "OFFSET") (pin "1") (pinfunction "1_1") (pintype "passive"))
      (node (ref "R38") (pin "2") (pinfunction "2_2") (pintype "passive"))
    )
    (net (code "57") (name "Net-(OFFSET1-Pad1)") (class "Default")
      (node (ref "OFFSET1") (pin "1") (pinfunction "1_1") (pintype "passive"))
      (node (ref "R27") (pin "2") (pinfunction "2_2") (pintype "passive"))
    )
    (net (code "58") (name "Net-(Q1A-B)") (class "Default")
      (node (ref "D1") (pin "A") (pinfunction "A_A") (pintype "passive"))
      (node (ref "Q1") (pin "2") (pinfunction "B_2") (pintype "passive"))
      (node (ref "V/OCT") (pin "2") (pinfunction "2_2") (pintype "passive"))
    )
    (net (code "59") (name "Net-(Q1A-E)") (class "Default")
      (node (ref "Q1") (pin "12") (pinfunction "E_12") (pintype "passive"))
      (node (ref "Q1") (pin "3") (pinfunction "E_3") (pintype "passive"))
      (node (ref "R10") (pin "2") (pinfunction "2_2") (pintype "passive"))
    )
    (net (code "60") (name "Net-(Q1C-B)") (class "Default")
      (node (ref "D107") (pin "A") (pinfunction "A_A") (pintype "passive"))
      (node (ref "Q1") (pin "6") (pinfunction "B_6") (pintype "passive"))
      (node (ref "V/OCT1") (pin "2") (pinfunction "2_2") (pintype "passive"))
    )
    (net (code "61") (name "Net-(Q1C-E)") (class "Default")
      (node (ref "Q1") (pin "10") (pinfunction "E_10") (pintype "passive"))
      (node (ref "Q1") (pin "5") (pinfunction "E_5") (pintype "passive"))
      (node (ref "R124") (pin "2") (pinfunction "2_2") (pintype "passive"))
    )
    (net (code "62") (name "Net-(R2-Pad2)") (class "Default")
      (node (ref "R2") (pin "2") (pinfunction "2_2") (pintype "passive"))
      (node (ref "V/OCT") (pin "1") (pinfunction "1_1") (pintype "passive"))
    )
    (net (code "63") (name "Net-(R122-Pad2)") (class "Default")
      (node (ref "R122") (pin "2") (pinfunction "2_2") (pintype "passive"))
      (node (ref "V/OCT1") (pin "1") (pinfunction "1_1") (pintype "passive"))
    )
    (net (code "64") (name "Net-(U1A-OUT)") (class "Default")
      (node (ref "R7") (pin "2") (pinfunction "2_2") (pintype "passive"))
      (node (ref "U1") (pin "1") (pinfunction "OUT_1") (pintype "output"))
      (node (ref "V/OCT") (pin "3") (pinfunction "3_3") (pintype "passive"))
    )
    (net (code "65") (name "Net-(U1B-OUT)") (class "Default")
      (node (ref "C1") (pin "1") (pinfunction "1_1") (pintype "passive"))
      (node (ref "HIGH_FREQ") (pin "2") (pinfunction "2_2") (pintype "passive"))
      (node (ref "HIGH_FREQ") (pin "3") (pinfunction "3_3") (pintype "passive"))
      (node (ref "R10") (pin "1") (pinfunction "1_1") (pintype "passive"))
      (node (ref "U1") (pin "7") (pinfunction "OUT_7") (pintype "output"))
    )
    (net (code "66") (name "Net-(U2A--IN)") (class "Default")
      (node (ref "OFFSET") (pin "2") (pinfunction "2_2") (pintype "passive"))
      (node (ref "OFFSET") (pin "3") (pinfunction "3_3") (pintype "passive"))
      (node (ref "R25") (pin "1") (pinfunction "1_1") (pintype "passive"))
      (node (ref "R39") (pin "1") (pinfunction "1_1") (pintype "passive"))
      (node (ref "U2") (pin "2") (pinfunction "-IN_2") (pintype "input"))
    )
    (net (code "67") (name "Net-(U2A-OUT)") (class "Default")
      (node (ref "R39") (pin "2") (pinfunction "2_2") (pintype "passive"))
      (node (ref "R4") (pin "1") (pinfunction "1_1") (pintype "passive"))
      (node (ref "U2") (pin "1") (pinfunction "OUT_1") (pintype "output"))
    )
    (net (code "68") (name "Net-(U2B-+IN)") (class "Default")
      (node (ref "R45") (pin "2") (pinfunction "2_2") (pintype "passive"))
      (node (ref "R8") (pin "1") (pinfunction "1_1") (pintype "passive"))
      (node (ref "U2") (pin "5") (pinfunction "+IN_5") (pintype "input"))
    )
    (net (code "69") (name "Net-(U2B--IN)") (class "Default")
      (node (ref "R18") (pin "1") (pinfunction "1_1") (pintype "passive"))
      (node (ref "R19") (pin "2") (pinfunction "2_2") (pintype "passive"))
      (node (ref "U2") (pin "6") (pinfunction "-IN_6") (pintype "input"))
    )
    (net (code "70") (name "Net-(U2B-OUT)") (class "Default")
      (node (ref "R45") (pin "1") (pinfunction "1_1") (pintype "passive"))
      (node (ref "R9") (pin "2") (pinfunction "2_2") (pintype "passive"))
      (node (ref "U2") (pin "7") (pinfunction "OUT_7") (pintype "output"))
    )
    (net (code "71") (name "Net-(U2C-OUT)") (class "Default")
      (node (ref "D2") (pin "A") (pinfunction "A_A") (pintype "passive"))
      (node (ref "D3") (pin "C") (pinfunction "C_C") (pintype "passive"))
      (node (ref "U2") (pin "8") (pinfunction "OUT_8") (pintype "output"))
    )
    (net (code "72") (name "Net-(U2D--IN)") (class "Default")
      (node (ref "R15") (pin "1") (pinfunction "1_1") (pintype "passive"))
      (node (ref "R16") (pin "2") (pinfunction "2_2") (pintype "passive"))
      (node (ref "U2") (pin "13") (pinfunction "-IN_13") (pintype "input"))
    )
    (net (code "73") (name "Net-(U3A-OUT)") (class "Default")
      (node (ref "R101") (pin "2") (pinfunction "2_2") (pintype "passive"))
      (node (ref "U3") (pin "1") (pinfunction "OUT_1") (pintype "output"))
      (node (ref "V/OCT1") (pin "3") (pinfunction "3_3") (pintype "passive"))
    )
    (net (code "74") (name "Net-(U3B-OUT)") (class "Default")
      (node (ref "C108") (pin "1") (pinfunction "1_1") (pintype "passive"))
      (node (ref "HIGH_FREQ1") (pin "2") (pinfunction "2_2") (pintype "passive"))
      (node (ref "HIGH_FREQ1") (pin "3") (pinfunction "3_3") (pintype "passive"))
      (node (ref "R124") (pin "1") (pinfunction "1_1") (pintype "passive"))
      (node (ref "U3") (pin "7") (pinfunction "OUT_7") (pintype "output"))
    )
    (net (code "75") (name "Net-(U4A--IN)") (class "Default")
      (node (ref "OFFSET1") (pin "2") (pinfunction "2_2") (pintype "passive"))
      (node (ref "OFFSET1") (pin "3") (pinfunction "3_3") (pintype "passive"))
      (node (ref "R103") (pin "1") (pinfunction "1_1") (pintype "passive"))
      (node (ref "R128") (pin "1") (pinfunction "1_1") (pintype "passive"))
      (node (ref "U4") (pin "2") (pinfunction "-IN_2") (pintype "input"))
    )
    (net (code "76") (name "Net-(U4A-OUT)") (class "Default")
      (node (ref "R118") (pin "1") (pinfunction "1_1") (pintype "passive"))
      (node (ref "R128") (pin "2") (pinfunction "2_2") (pintype "passive"))
      (node (ref "U4") (pin "1") (pinfunction "OUT_1") (pintype "output"))
    )
    (net (code "77") (name "Net-(U4B-+IN)") (class "Default")
      (node (ref "R132") (pin "1") (pinfunction "1_1") (pintype "passive"))
      (node (ref "R149") (pin "2") (pinfunction "2_2") (pintype "passive"))
      (node (ref "U4") (pin "5") (pinfunction "+IN_5") (pintype "input"))
    )
    (net (code "78") (name "Net-(U4B--IN)") (class "Default")
      (node (ref "R152") (pin "1") (pinfunction "1_1") (pintype "passive"))
      (node (ref "R153") (pin "2") (pinfunction "2_2") (pintype "passive"))
      (node (ref "U4") (pin "6") (pinfunction "-IN_6") (pintype "input"))
    )
    (net (code "79") (name "Net-(U4B-OUT)") (class "Default")
      (node (ref "R149") (pin "1") (pinfunction "1_1") (pintype "passive"))
      (node (ref "R150") (pin "2") (pinfunction "2_2") (pintype "passive"))
      (node (ref "U4") (pin "7") (pinfunction "OUT_7") (pintype "output"))
    )
    (net (code "80") (name "Net-(U4C-OUT)") (class "Default")
      (node (ref "D112") (pin "A") (pinfunction "A_A") (pintype "passive"))
      (node (ref "D113") (pin "C") (pinfunction "C_C") (pintype "passive"))
      (node (ref "U4") (pin "8") (pinfunction "OUT_8") (pintype "output"))
    )
    (net (code "81") (name "Net-(U4D--IN)") (class "Default")
      (node (ref "R129") (pin "2") (pinfunction "2_2") (pintype "passive"))
      (node (ref "R133") (pin "1") (pinfunction "1_1") (pintype "passive"))
      (node (ref "U4") (pin "13") (pinfunction "-IN_13") (pintype "input"))
    )
    (net (code "82") (name "PITCH_CV_1") (class "Default")
      (node (ref "JP1") (pin "7") (pinfunction "7_7") (pintype "passive"))
      (node (ref "R7") (pin "1") (pinfunction "1_1") (pintype "passive"))
      (node (ref "U1") (pin "2") (pinfunction "-IN_2") (pintype "input"))
    )
    (net (code "83") (name "PITCH_CV_2") (class "Default")
      (node (ref "JP3") (pin "7") (pinfunction "7_7") (pintype "passive"))
      (node (ref "R101") (pin "1") (pinfunction "1_1") (pintype "passive"))
      (node (ref "U3") (pin "2") (pinfunction "-IN_2") (pintype "input"))
    )
    (net (code "84") (name "SINE_TRI_OUT_1") (class "Default")
      (node (ref "JP1") (pin "3") (pinfunction "3_3") (pintype "passive"))
      (node (ref "R4") (pin "2") (pinfunction "2_2") (pintype "passive"))
    )
    (net (code "85") (name "SINE_TRI_OUT_2") (class "Default")
      (node (ref "JP3") (pin "3") (pinfunction "3_3") (pintype "passive"))
      (node (ref "R118") (pin "2") (pinfunction "2_2") (pintype "passive"))
    )
    (net (code "86") (name "SKEW_IN_1") (class "Default")
      (node (ref "D2") (pin "C") (pinfunction "C_C") (pintype "passive"))
      (node (ref "JP1") (pin "5") (pinfunction "5_5") (pintype "passive"))
      (node (ref "R41") (pin "2") (pinfunction "2_2") (pintype "passive"))
      (node (ref "R44") (pin "1") (pinfunction "1_1") (pintype "passive"))
      (node (ref "U2") (pin "9") (pinfunction "-IN_9") (pintype "input"))
    )
    (net (code "87") (name "SKEW_IN_2") (class "Default")
      (node (ref "D112") (pin "C") (pinfunction "C_C") (pintype "passive"))
      (node (ref "JP3") (pin "5") (pinfunction "5_5") (pintype "passive"))
      (node (ref "R134") (pin "2") (pinfunction "2_2") (pintype "passive"))
      (node (ref "R155") (pin "1") (pinfunction "1_1") (pintype "passive"))
      (node (ref "U4") (pin "9") (pinfunction "-IN_9") (pintype "input"))
    )
    (net (code "88") (name "SQR_OUT_1") (class "Default")
      (node (ref "JP1") (pin "2") (pinfunction "2_2") (pintype "passive"))
      (node (ref "R6") (pin "2") (pinfunction "2_2") (pintype "passive"))
      (node (ref "R9") (pin "1") (pinfunction "1_1") (pintype "passive"))
    )
    (net (code "89") (name "SQR_OUT_2") (class "Default")
      (node (ref "JP3") (pin "2") (pinfunction "2_2") (pintype "passive"))
      (node (ref "R150") (pin "1") (pinfunction "1_1") (pintype "passive"))
      (node (ref "R151") (pin "2") (pinfunction "2_2") (pintype "passive"))
    )
    (net (code "90") (name "SYNC_IN_1") (class "Default")
      (node (ref "C2") (pin "1") (pinfunction "1_1") (pintype "passive"))
      (node (ref "JP1") (pin "6") (pinfunction "6_6") (pintype "passive"))
    )
    (net (code "91") (name "SYNC_IN_2") (class "Default")
      (node (ref "C12") (pin "1") (pinfunction "1_1") (pintype "passive"))
      (node (ref "JP3") (pin "6") (pinfunction "6_6") (pintype "passive"))
    )
    (net (code "92") (name "unconnected-(JP1-Pad1)") (class "Default")
      (node (ref "JP1") (pin "1") (pinfunction "1_1") (pintype "passive"))
    )
    (net (code "93") (name "unconnected-(JP3-Pad1)") (class "Default")
      (node (ref "JP3") (pin "1") (pinfunction "1_1") (pintype "passive"))
    )
  )
)
